# LoRa_ST_v4_1.net
KiCad netlist of a schematic drawn in EAGLE
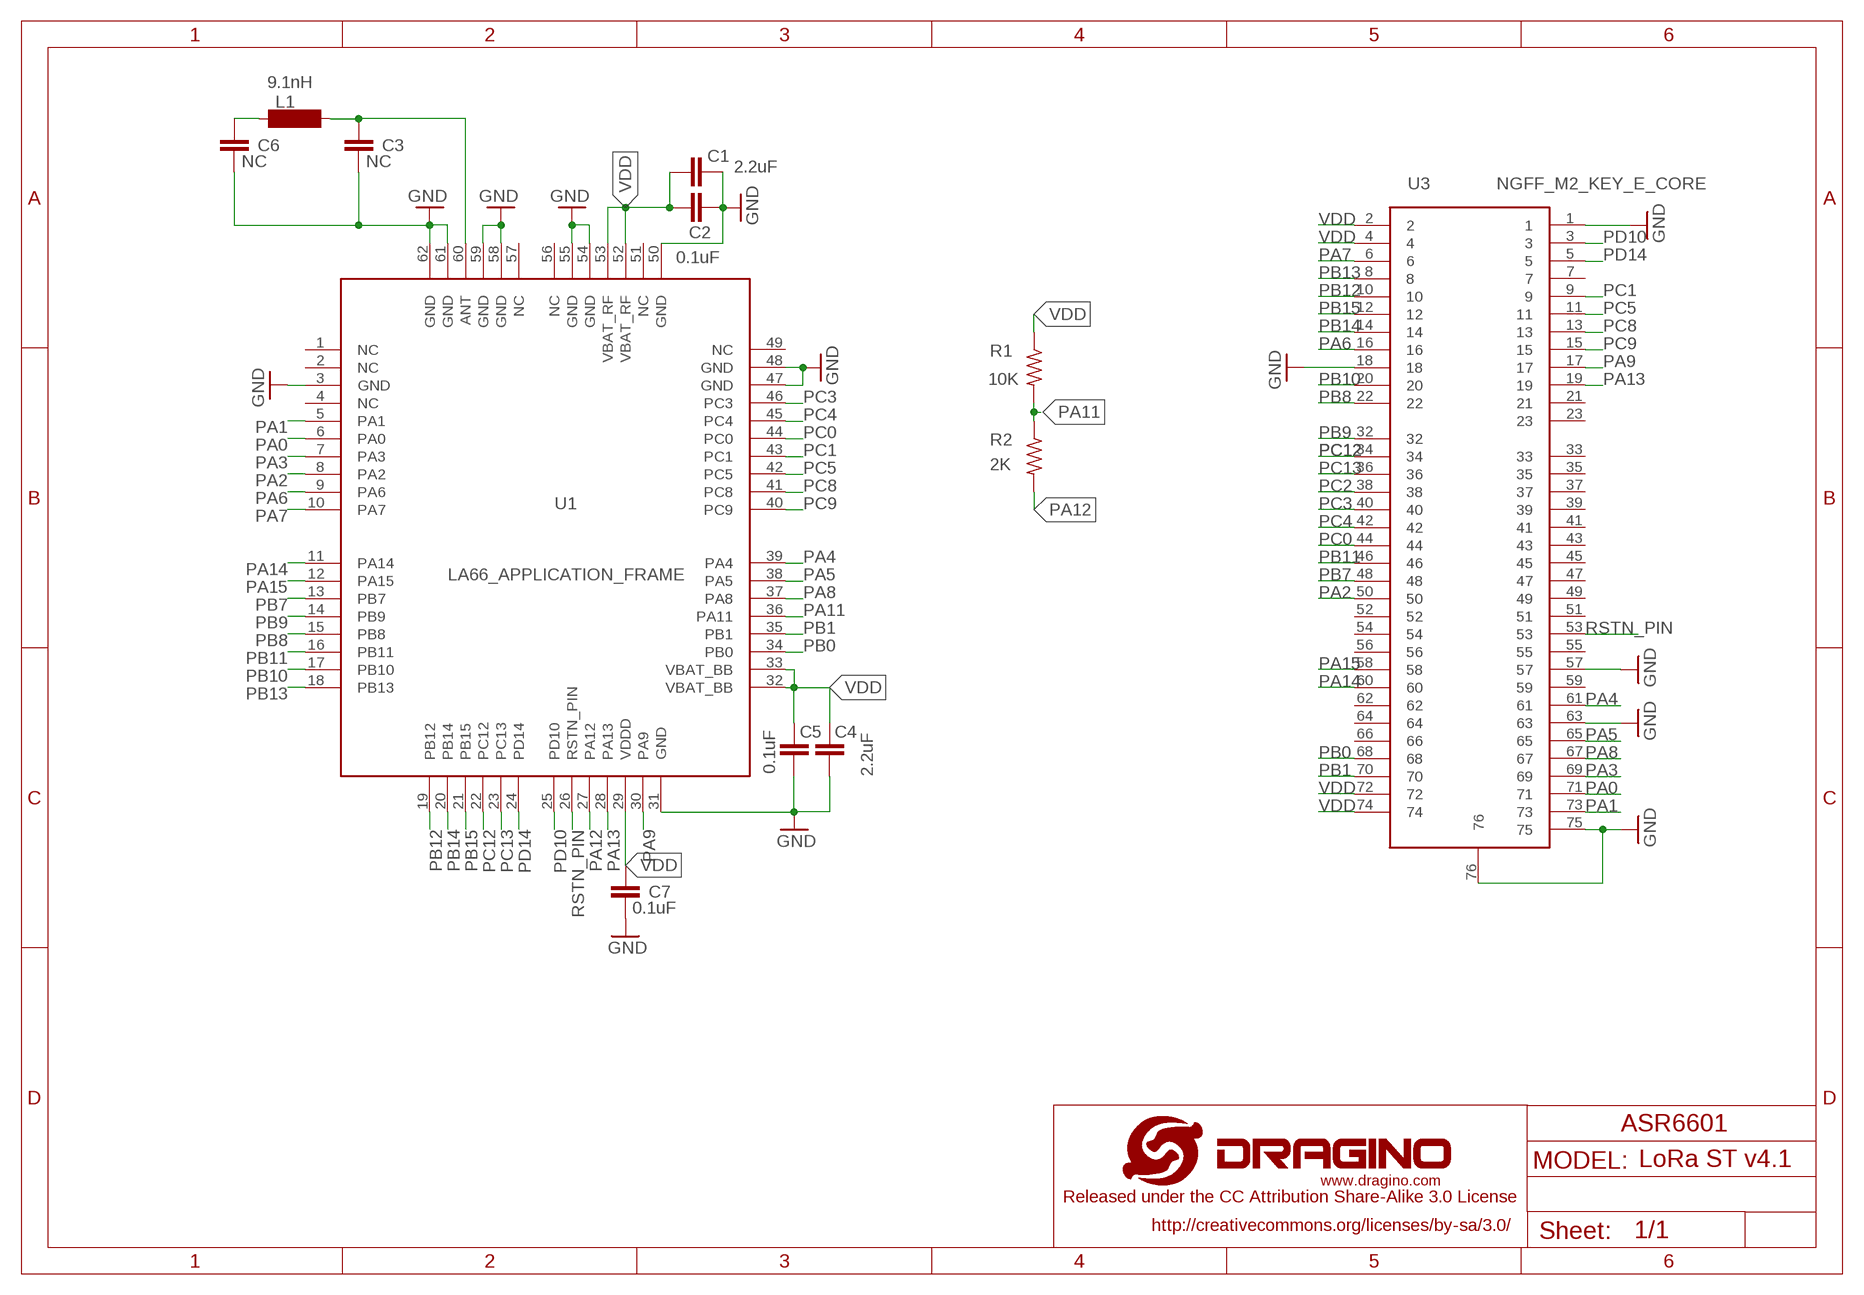
[diagram p0: schematic, sheet 1]

(export (version "E")
  (design (tool "Eeschema 10.0.6"))
  (components
    (comp (ref "C1")
      (value "2.2uF")
      (footprint "eagle-import:C0402")
      (libsource (lib "eagle-import") (part "C-EUC0402"))
    )
    (comp (ref "C2")
      (value "0.1uF")
      (footprint "eagle-import:C0402")
      (libsource (lib "eagle-import") (part "C-EUC0402"))
    )
    (comp (ref "C3")
      (value "NC")
      (footprint "eagle-import:C0402")
      (libsource (lib "eagle-import") (part "C-EUC0402"))
    )
    (comp (ref "C4")
      (value "2.2uF")
      (footprint "eagle-import:C0402")
      (libsource (lib "eagle-import") (part "C-EUC0402"))
    )
    (comp (ref "C5")
      (value "0.1uF")
      (footprint "eagle-import:C0402")
      (libsource (lib "eagle-import") (part "C-EUC0402"))
    )
    (comp (ref "C6")
      (value "NC")
      (footprint "eagle-import:C0402")
      (libsource (lib "eagle-import") (part "C-EUC0402"))
    )
    (comp (ref "C7")
      (value "0.1uF")
      (footprint "eagle-import:C0402")
      (libsource (lib "eagle-import") (part "C-EUC0402"))
    )
    (comp (ref "L1")
      (value "9.1nH")
      (footprint "eagle-import:L-0402")
      (libsource (lib "eagle-import") (part "L1"))
    )
    (comp (ref "R1")
      (value "10K")
      (footprint "eagle-import:R0402")
      (libsource (lib "eagle-import") (part "R-US_R0402"))
    )
    (comp (ref "R2")
      (value "2K")
      (footprint "eagle-import:R0402")
      (libsource (lib "eagle-import") (part "R-US_R0402"))
    )
    (comp (ref "U1")
      (value "LA66_APPLICATION_FRAME")
      (footprint "eagle-import:LA66_APPLICATION_FRAME")
      (libsource (lib "eagle-import") (part "LA66_APPLICATION_FRAME"))
    )
    (comp (ref "U3")
      (value "NGFF_M2_KEY_E_CORE")
      (footprint "eagle-import:LORA_ST_PCB")
      (libsource (lib "eagle-import") (part "NGFF_M2_KEY_E_CORE"))
    )
  )
  (nets
    (net (code "1") (name "/PA0") (class "Default")
      (node (ref "U1") (pin "6") (pinfunction "PA0_6") (pintype "bidirectional"))
      (node (ref "U3") (pin "71") (pinfunction "71_71") (pintype "bidirectional"))
    )
    (net (code "2") (name "/PA1") (class "Default")
      (node (ref "U1") (pin "5") (pinfunction "PA1_5") (pintype "bidirectional"))
      (node (ref "U3") (pin "73") (pinfunction "73_73") (pintype "bidirectional"))
    )
    (net (code "3") (name "/PA2") (class "Default")
      (node (ref "U1") (pin "8") (pinfunction "PA2_8") (pintype "bidirectional"))
      (node (ref "U3") (pin "50") (pinfunction "50_50") (pintype "bidirectional"))
    )
    (net (code "4") (name "/PA3") (class "Default")
      (node (ref "U1") (pin "7") (pinfunction "PA3_7") (pintype "bidirectional"))
      (node (ref "U3") (pin "69") (pinfunction "69_69") (pintype "bidirectional"))
    )
    (net (code "5") (name "/PA4") (class "Default")
      (node (ref "U1") (pin "39") (pinfunction "PA4_39") (pintype "bidirectional"))
      (node (ref "U3") (pin "61") (pinfunction "61_61") (pintype "bidirectional"))
    )
    (net (code "6") (name "/PA5") (class "Default")
      (node (ref "U1") (pin "38") (pinfunction "PA5_38") (pintype "bidirectional"))
      (node (ref "U3") (pin "65") (pinfunction "65_65") (pintype "bidirectional"))
    )
    (net (code "7") (name "/PA6") (class "Default")
      (node (ref "U1") (pin "9") (pinfunction "PA6_9") (pintype "bidirectional"))
      (node (ref "U3") (pin "16") (pinfunction "16_16") (pintype "bidirectional"))
    )
    (net (code "8") (name "/PA7") (class "Default")
      (node (ref "U1") (pin "10") (pinfunction "PA7_10") (pintype "bidirectional"))
      (node (ref "U3") (pin "6") (pinfunction "6_6") (pintype "bidirectional"))
    )
    (net (code "9") (name "/PA8") (class "Default")
      (node (ref "U1") (pin "37") (pinfunction "PA8_37") (pintype "bidirectional"))
      (node (ref "U3") (pin "67") (pinfunction "67_67") (pintype "bidirectional"))
    )
    (net (code "10") (name "/PA9") (class "Default")
      (node (ref "U1") (pin "30") (pinfunction "PA9_30") (pintype "bidirectional"))
      (node (ref "U3") (pin "17") (pinfunction "17_17") (pintype "bidirectional"))
    )
    (net (code "11") (name "/PA13") (class "Default")
      (node (ref "U1") (pin "28") (pinfunction "PA13_28") (pintype "bidirectional"))
      (node (ref "U3") (pin "19") (pinfunction "19_19") (pintype "bidirectional"))
    )
    (net (code "12") (name "/PA14") (class "Default")
      (node (ref "U1") (pin "11") (pinfunction "PA14_11") (pintype "bidirectional"))
      (node (ref "U3") (pin "60") (pinfunction "60_60") (pintype "bidirectional"))
    )
    (net (code "13") (name "/PA15") (class "Default")
      (node (ref "U1") (pin "12") (pinfunction "PA15_12") (pintype "bidirectional"))
      (node (ref "U3") (pin "58") (pinfunction "58_58") (pintype "bidirectional"))
    )
    (net (code "14") (name "/PB0") (class "Default")
      (node (ref "U1") (pin "34") (pinfunction "PB0_34") (pintype "bidirectional"))
      (node (ref "U3") (pin "68") (pinfunction "68_68") (pintype "bidirectional"))
    )
    (net (code "15") (name "/PB1") (class "Default")
      (node (ref "U1") (pin "35") (pinfunction "PB1_35") (pintype "bidirectional"))
      (node (ref "U3") (pin "70") (pinfunction "70_70") (pintype "bidirectional"))
    )
    (net (code "16") (name "/PB7") (class "Default")
      (node (ref "U1") (pin "13") (pinfunction "PB7_13") (pintype "bidirectional"))
      (node (ref "U3") (pin "48") (pinfunction "48_48") (pintype "bidirectional"))
    )
    (net (code "17") (name "/PB8") (class "Default")
      (node (ref "U1") (pin "15") (pinfunction "PB8_15") (pintype "bidirectional"))
      (node (ref "U3") (pin "22") (pinfunction "22_22") (pintype "bidirectional"))
    )
    (net (code "18") (name "/PB9") (class "Default")
      (node (ref "U1") (pin "14") (pinfunction "PB9_14") (pintype "bidirectional"))
      (node (ref "U3") (pin "32") (pinfunction "32_32") (pintype "bidirectional"))
    )
    (net (code "19") (name "/PB10") (class "Default")
      (node (ref "U1") (pin "17") (pinfunction "PB10_17") (pintype "bidirectional"))
      (node (ref "U3") (pin "20") (pinfunction "20_20") (pintype "bidirectional"))
    )
    (net (code "20") (name "/PB11") (class "Default")
      (node (ref "U1") (pin "16") (pinfunction "PB11_16") (pintype "bidirectional"))
      (node (ref "U3") (pin "46") (pinfunction "46_46") (pintype "bidirectional"))
    )
    (net (code "21") (name "/PB12") (class "Default")
      (node (ref "U1") (pin "19") (pinfunction "PB12_19") (pintype "bidirectional"))
      (node (ref "U3") (pin "10") (pinfunction "10_10") (pintype "bidirectional"))
    )
    (net (code "22") (name "/PB13") (class "Default")
      (node (ref "U1") (pin "18") (pinfunction "PB13_18") (pintype "bidirectional"))
      (node (ref "U3") (pin "8") (pinfunction "8_8") (pintype "bidirectional"))
    )
    (net (code "23") (name "/PB14") (class "Default")
      (node (ref "U1") (pin "20") (pinfunction "PB14_20") (pintype "bidirectional"))
      (node (ref "U3") (pin "14") (pinfunction "14_14") (pintype "bidirectional"))
    )
    (net (code "24") (name "/PB15") (class "Default")
      (node (ref "U1") (pin "21") (pinfunction "PB15_21") (pintype "bidirectional"))
      (node (ref "U3") (pin "12") (pinfunction "12_12") (pintype "bidirectional"))
    )
    (net (code "25") (name "/PC0") (class "Default")
      (node (ref "U1") (pin "44") (pinfunction "PC0_44") (pintype "bidirectional"))
      (node (ref "U3") (pin "44") (pinfunction "44_44") (pintype "bidirectional"))
    )
    (net (code "26") (name "/PC1") (class "Default")
      (node (ref "U1") (pin "43") (pinfunction "PC1_43") (pintype "bidirectional"))
      (node (ref "U3") (pin "9") (pinfunction "9_9") (pintype "bidirectional"))
    )
    (net (code "27") (name "/PC2") (class "Default")
      (node (ref "U3") (pin "38") (pinfunction "38_38") (pintype "bidirectional"))
    )
    (net (code "28") (name "/PC3") (class "Default")
      (node (ref "U1") (pin "46") (pinfunction "PC3_46") (pintype "bidirectional"))
      (node (ref "U3") (pin "40") (pinfunction "40_40") (pintype "bidirectional"))
    )
    (net (code "29") (name "/PC4") (class "Default")
      (node (ref "U1") (pin "45") (pinfunction "PC4_45") (pintype "bidirectional"))
      (node (ref "U3") (pin "42") (pinfunction "42_42") (pintype "bidirectional"))
    )
    (net (code "30") (name "/PC5") (class "Default")
      (node (ref "U1") (pin "42") (pinfunction "PC5_42") (pintype "bidirectional"))
      (node (ref "U3") (pin "11") (pinfunction "11_11") (pintype "bidirectional"))
    )
    (net (code "31") (name "/PC8") (class "Default")
      (node (ref "U1") (pin "41") (pinfunction "PC8_41") (pintype "bidirectional"))
      (node (ref "U3") (pin "13") (pinfunction "13_13") (pintype "bidirectional"))
    )
    (net (code "32") (name "/PC9") (class "Default")
      (node (ref "U1") (pin "40") (pinfunction "PC9_40") (pintype "bidirectional"))
      (node (ref "U3") (pin "15") (pinfunction "15_15") (pintype "bidirectional"))
    )
    (net (code "33") (name "/PC12") (class "Default")
      (node (ref "U1") (pin "22") (pinfunction "PC12_22") (pintype "bidirectional"))
      (node (ref "U3") (pin "34") (pinfunction "34_34") (pintype "bidirectional"))
    )
    (net (code "34") (name "/PC13") (class "Default")
      (node (ref "U1") (pin "23") (pinfunction "PC13_23") (pintype "bidirectional"))
      (node (ref "U3") (pin "36") (pinfunction "36_36") (pintype "bidirectional"))
    )
    (net (code "35") (name "/PD10") (class "Default")
      (node (ref "U1") (pin "25") (pinfunction "PD10_25") (pintype "bidirectional"))
      (node (ref "U3") (pin "3") (pinfunction "3_3") (pintype "bidirectional"))
    )
    (net (code "36") (name "/PD14") (class "Default")
      (node (ref "U1") (pin "24") (pinfunction "PD14_24") (pintype "bidirectional"))
      (node (ref "U3") (pin "5") (pinfunction "5_5") (pintype "bidirectional"))
    )
    (net (code "37") (name "/RSTN_PIN") (class "Default")
      (node (ref "U1") (pin "26") (pinfunction "RSTN_PIN_26") (pintype "bidirectional"))
      (node (ref "U3") (pin "53") (pinfunction "53_53") (pintype "bidirectional"))
    )
    (net (code "38") (name "GND") (class "Default")
      (node (ref "C1") (pin "1") (pinfunction "1_1") (pintype "passive"))
      (node (ref "C2") (pin "2") (pinfunction "2_2") (pintype "passive"))
      (node (ref "C3") (pin "1") (pinfunction "1_1") (pintype "passive"))
      (node (ref "C4") (pin "2") (pinfunction "2_2") (pintype "passive"))
      (node (ref "C5") (pin "1") (pinfunction "1_1") (pintype "passive"))
      (node (ref "C6") (pin "1") (pinfunction "1_1") (pintype "passive"))
      (node (ref "C7") (pin "1") (pinfunction "1_1") (pintype "passive"))
      (node (ref "U1") (pin "3") (pinfunction "GND_3") (pintype "bidirectional"))
      (node (ref "U1") (pin "31") (pinfunction "GND_31") (pintype "bidirectional"))
      (node (ref "U1") (pin "47") (pinfunction "GND_47") (pintype "bidirectional"))
      (node (ref "U1") (pin "48") (pinfunction "GND_48") (pintype "bidirectional"))
      (node (ref "U1") (pin "50") (pinfunction "GND_50") (pintype "bidirectional"))
      (node (ref "U1") (pin "54") (pinfunction "GND_54") (pintype "bidirectional"))
      (node (ref "U1") (pin "55") (pinfunction "GND_55") (pintype "bidirectional"))
      (node (ref "U1") (pin "58") (pinfunction "GND_58") (pintype "bidirectional"))
      (node (ref "U1") (pin "59") (pinfunction "GND_59") (pintype "bidirectional"))
      (node (ref "U1") (pin "61") (pinfunction "GND_61") (pintype "bidirectional"))
      (node (ref "U1") (pin "62") (pinfunction "GND_62") (pintype "bidirectional"))
      (node (ref "U3") (pin "1") (pinfunction "1_1") (pintype "bidirectional"))
      (node (ref "U3") (pin "18") (pinfunction "18_18") (pintype "bidirectional"))
      (node (ref "U3") (pin "57") (pinfunction "57_57") (pintype "bidirectional"))
      (node (ref "U3") (pin "63") (pinfunction "63_63") (pintype "bidirectional"))
      (node (ref "U3") (pin "75") (pinfunction "75_75") (pintype "bidirectional"))
      (node (ref "U3") (pin "76") (pinfunction "76_76") (pintype "bidirectional"))
    )
    (net (code "39") (name "Net-(C6-Pad2)") (class "Default")
      (node (ref "C6") (pin "2") (pinfunction "2_2") (pintype "passive"))
      (node (ref "L1") (pin "2") (pinfunction "2_2") (pintype "passive"))
    )
    (net (code "40") (name "Net-(U1-ANT)") (class "Default")
      (node (ref "C3") (pin "2") (pinfunction "2_2") (pintype "passive"))
      (node (ref "L1") (pin "1") (pinfunction "1_1") (pintype "passive"))
      (node (ref "U1") (pin "60") (pinfunction "ANT_60") (pintype "bidirectional"))
    )
    (net (code "41") (name "PA11") (class "Default")
      (node (ref "R1") (pin "2") (pinfunction "2_2") (pintype "passive"))
      (node (ref "R2") (pin "1") (pinfunction "1_1") (pintype "passive"))
      (node (ref "U1") (pin "36") (pinfunction "PA11_36") (pintype "bidirectional"))
    )
    (net (code "42") (name "PA12") (class "Default")
      (node (ref "R2") (pin "2") (pinfunction "2_2") (pintype "passive"))
      (node (ref "U1") (pin "27") (pinfunction "PA12_27") (pintype "bidirectional"))
    )
    (net (code "43") (name "VDD") (class "Default")
      (node (ref "C1") (pin "2") (pinfunction "2_2") (pintype "passive"))
      (node (ref "C2") (pin "1") (pinfunction "1_1") (pintype "passive"))
      (node (ref "C4") (pin "1") (pinfunction "1_1") (pintype "passive"))
      (node (ref "C5") (pin "2") (pinfunction "2_2") (pintype "passive"))
      (node (ref "C7") (pin "2") (pinfunction "2_2") (pintype "passive"))
      (node (ref "R1") (pin "1") (pinfunction "1_1") (pintype "passive"))
      (node (ref "U1") (pin "29") (pinfunction "VDDD_29") (pintype "bidirectional"))
      (node (ref "U1") (pin "32") (pinfunction "VBAT_BB_32") (pintype "bidirectional"))
      (node (ref "U1") (pin "33") (pinfunction "VBAT_BB_33") (pintype "bidirectional"))
      (node (ref "U1") (pin "52") (pinfunction "VBAT_RF_52") (pintype "bidirectional"))
      (node (ref "U1") (pin "53") (pinfunction "VBAT_RF_53") (pintype "bidirectional"))
      (node (ref "U3") (pin "2") (pinfunction "2_2") (pintype "bidirectional"))
      (node (ref "U3") (pin "4") (pinfunction "4_4") (pintype "bidirectional"))
      (node (ref "U3") (pin "72") (pinfunction "72_72") (pintype "bidirectional"))
      (node (ref "U3") (pin "74") (pinfunction "74_74") (pintype "bidirectional"))
    )
    (net (code "44") (name "unconnected-(U1-NC-Pad1)") (class "Default")
      (node (ref "U1") (pin "1") (pinfunction "NC_1") (pintype "bidirectional"))
    )
    (net (code "45") (name "unconnected-(U1-NC-Pad2)") (class "Default")
      (node (ref "U1") (pin "2") (pinfunction "NC_2") (pintype "bidirectional"))
    )
    (net (code "46") (name "unconnected-(U1-NC-Pad4)") (class "Default")
      (node (ref "U1") (pin "4") (pinfunction "NC_4") (pintype "bidirectional"))
    )
    (net (code "47") (name "unconnected-(U1-NC-Pad49)") (class "Default")
      (node (ref "U1") (pin "49") (pinfunction "NC_49") (pintype "bidirectional"))
    )
    (net (code "48") (name "unconnected-(U1-NC-Pad51)") (class "Default")
      (node (ref "U1") (pin "51") (pinfunction "NC_51") (pintype "bidirectional"))
    )
    (net (code "49") (name "unconnected-(U1-NC-Pad56)") (class "Default")
      (node (ref "U1") (pin "56") (pinfunction "NC_56") (pintype "bidirectional"))
    )
    (net (code "50") (name "unconnected-(U1-NC-Pad57)") (class "Default")
      (node (ref "U1") (pin "57") (pinfunction "NC_57") (pintype "bidirectional"))
    )
    (net (code "51") (name "unconnected-(U3-Pad7)") (class "Default")
      (node (ref "U3") (pin "7") (pinfunction "7_7") (pintype "bidirectional"))
    )
    (net (code "52") (name "unconnected-(U3-Pad21)") (class "Default")
      (node (ref "U3") (pin "21") (pinfunction "21_21") (pintype "bidirectional"))
    )
    (net (code "53") (name "unconnected-(U3-Pad23)") (class "Default")
      (node (ref "U3") (pin "23") (pinfunction "23_23") (pintype "bidirectional"))
    )
    (net (code "54") (name "unconnected-(U3-Pad33)") (class "Default")
      (node (ref "U3") (pin "33") (pinfunction "33_33") (pintype "bidirectional"))
    )
    (net (code "55") (name "unconnected-(U3-Pad35)") (class "Default")
      (node (ref "U3") (pin "35") (pinfunction "35_35") (pintype "bidirectional"))
    )
    (net (code "56") (name "unconnected-(U3-Pad37)") (class "Default")
      (node (ref "U3") (pin "37") (pinfunction "37_37") (pintype "bidirectional"))
    )
    (net (code "57") (name "unconnected-(U3-Pad39)") (class "Default")
      (node (ref "U3") (pin "39") (pinfunction "39_39") (pintype "bidirectional"))
    )
    (net (code "58") (name "unconnected-(U3-Pad41)") (class "Default")
      (node (ref "U3") (pin "41") (pinfunction "41_41") (pintype "bidirectional"))
    )
    (net (code "59") (name "unconnected-(U3-Pad43)") (class "Default")
      (node (ref "U3") (pin "43") (pinfunction "43_43") (pintype "bidirectional"))
    )
    (net (code "60") (name "unconnected-(U3-Pad45)") (class "Default")
      (node (ref "U3") (pin "45") (pinfunction "45_45") (pintype "bidirectional"))
    )
    (net (code "61") (name "unconnected-(U3-Pad47)") (class "Default")
      (node (ref "U3") (pin "47") (pinfunction "47_47") (pintype "bidirectional"))
    )
    (net (code "62") (name "unconnected-(U3-Pad49)") (class "Default")
      (node (ref "U3") (pin "49") (pinfunction "49_49") (pintype "bidirectional"))
    )
    (net (code "63") (name "unconnected-(U3-Pad51)") (class "Default")
      (node (ref "U3") (pin "51") (pinfunction "51_51") (pintype "bidirectional"))
    )
    (net (code "64") (name "unconnected-(U3-Pad52)") (class "Default")
      (node (ref "U3") (pin "52") (pinfunction "52_52") (pintype "bidirectional"))
    )
    (net (code "65") (name "unconnected-(U3-Pad54)") (class "Default")
      (node (ref "U3") (pin "54") (pinfunction "54_54") (pintype "bidirectional"))
    )
    (net (code "66") (name "unconnected-(U3-Pad55)") (class "Default")
      (node (ref "U3") (pin "55") (pinfunction "55_55") (pintype "bidirectional"))
    )
    (net (code "67") (name "unconnected-(U3-Pad56)") (class "Default")
      (node (ref "U3") (pin "56") (pinfunction "56_56") (pintype "bidirectional"))
    )
    (net (code "68") (name "unconnected-(U3-Pad59)") (class "Default")
      (node (ref "U3") (pin "59") (pinfunction "59_59") (pintype "bidirectional"))
    )
    (net (code "69") (name "unconnected-(U3-Pad62)") (class "Default")
      (node (ref "U3") (pin "62") (pinfunction "62_62") (pintype "bidirectional"))
    )
    (net (code "70") (name "unconnected-(U3-Pad64)") (class "Default")
      (node (ref "U3") (pin "64") (pinfunction "64_64") (pintype "bidirectional"))
    )
    (net (code "71") (name "unconnected-(U3-Pad66)") (class "Default")
      (node (ref "U3") (pin "66") (pinfunction "66_66") (pintype "bidirectional"))
    )
  )
)
